# power_Section1_0.net
KiCad netlist of a schematic drawn in EAGLE
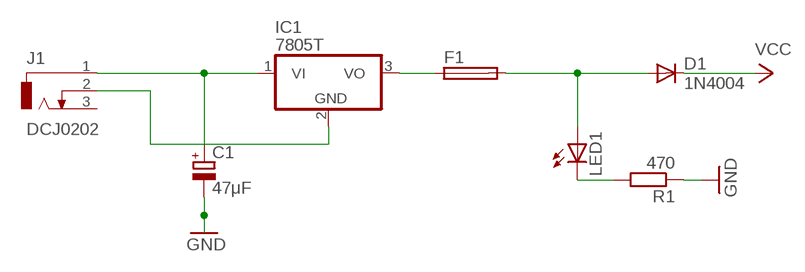
[diagram p0: schematic, sheet 1]

(export (version "E")
  (design (tool "Eeschema 10.0.6"))
  (components
    (comp (ref "C1")
      (value "47μF")
      (footprint "eagle-import:E2,5-5")
      (libsource (lib "eagle-import") (part "CPOL-EUE2.5-5"))
    )
    (comp (ref "D1")
      (value "1N4004")
      (footprint "eagle-import:DO41-10")
      (libsource (lib "eagle-import") (part "1N4004"))
    )
    (comp (ref "F1")
      (value "F457")
      (footprint "eagle-import:F457")
      (libsource (lib "eagle-import") (part "F457"))
    )
    (comp (ref "IC1")
      (value "7805T")
      (footprint "eagle-import:TO220H")
      (libsource (lib "eagle-import") (part "78T05"))
    )
    (comp (ref "J1")
      (value "DCJ0202")
      (footprint "eagle-import:DCJ0202")
      (libsource (lib "eagle-import") (part "DCJ0202"))
    )
    (comp (ref "LED1")
      (value "LED5MM")
      (footprint "eagle-import:LED5MM")
      (libsource (lib "eagle-import") (part "LED5MM"))
    )
    (comp (ref "R1")
      (value "470")
      (footprint "eagle-import:0207_10")
      (libsource (lib "eagle-import") (part "R-EU_0207/10"))
    )
  )
  (nets
    (net (code "1") (name "GND") (class "Default")
      (node (ref "C1") (pin "-") (pinfunction "-_-") (pintype "passive"))
      (node (ref "R1") (pin "1") (pinfunction "1_1") (pintype "passive"))
    )
    (net (code "2") (name "Net-(D1-PadA)") (class "Default")
      (node (ref "D1") (pin "A") (pinfunction "A_A") (pintype "passive"))
      (node (ref "F1") (pin "2") (pinfunction "2_2") (pintype "passive"))
      (node (ref "LED1") (pin "A") (pinfunction "A_A") (pintype "passive"))
    )
    (net (code "3") (name "Net-(IC1-GND)") (class "Default")
      (node (ref "IC1") (pin "2") (pinfunction "GND_2") (pintype "passive"))
      (node (ref "J1") (pin "2") (pinfunction "2_2") (pintype "passive"))
    )
    (net (code "4") (name "Net-(IC1-VI)") (class "Default")
      (node (ref "C1") (pin "+") (pinfunction "+_+") (pintype "passive"))
      (node (ref "IC1") (pin "1") (pinfunction "VI_1") (pintype "input"))
      (node (ref "J1") (pin "1") (pinfunction "1_1") (pintype "passive"))
    )
    (net (code "5") (name "Net-(IC1-VO)") (class "Default")
      (node (ref "F1") (pin "1") (pinfunction "1_1") (pintype "passive"))
      (node (ref "IC1") (pin "3") (pinfunction "VO_3") (pintype "passive"))
    )
    (net (code "6") (name "Net-(LED1-C)") (class "Default")
      (node (ref "LED1") (pin "K") (pinfunction "C_K") (pintype "passive"))
      (node (ref "R1") (pin "2") (pinfunction "2_2") (pintype "passive"))
    )
    (net (code "7") (name "VCC") (class "Default")
      (node (ref "D1") (pin "C") (pinfunction "C_C") (pintype "passive"))
    )
    (net (code "8") (name "unconnected-(J1-Pad3)") (class "Default")
      (node (ref "J1") (pin "3") (pinfunction "3_3") (pintype "passive"))
    )
  )
)
